# HW1_13.net
KiCad netlist of a schematic drawn in EasyEDA
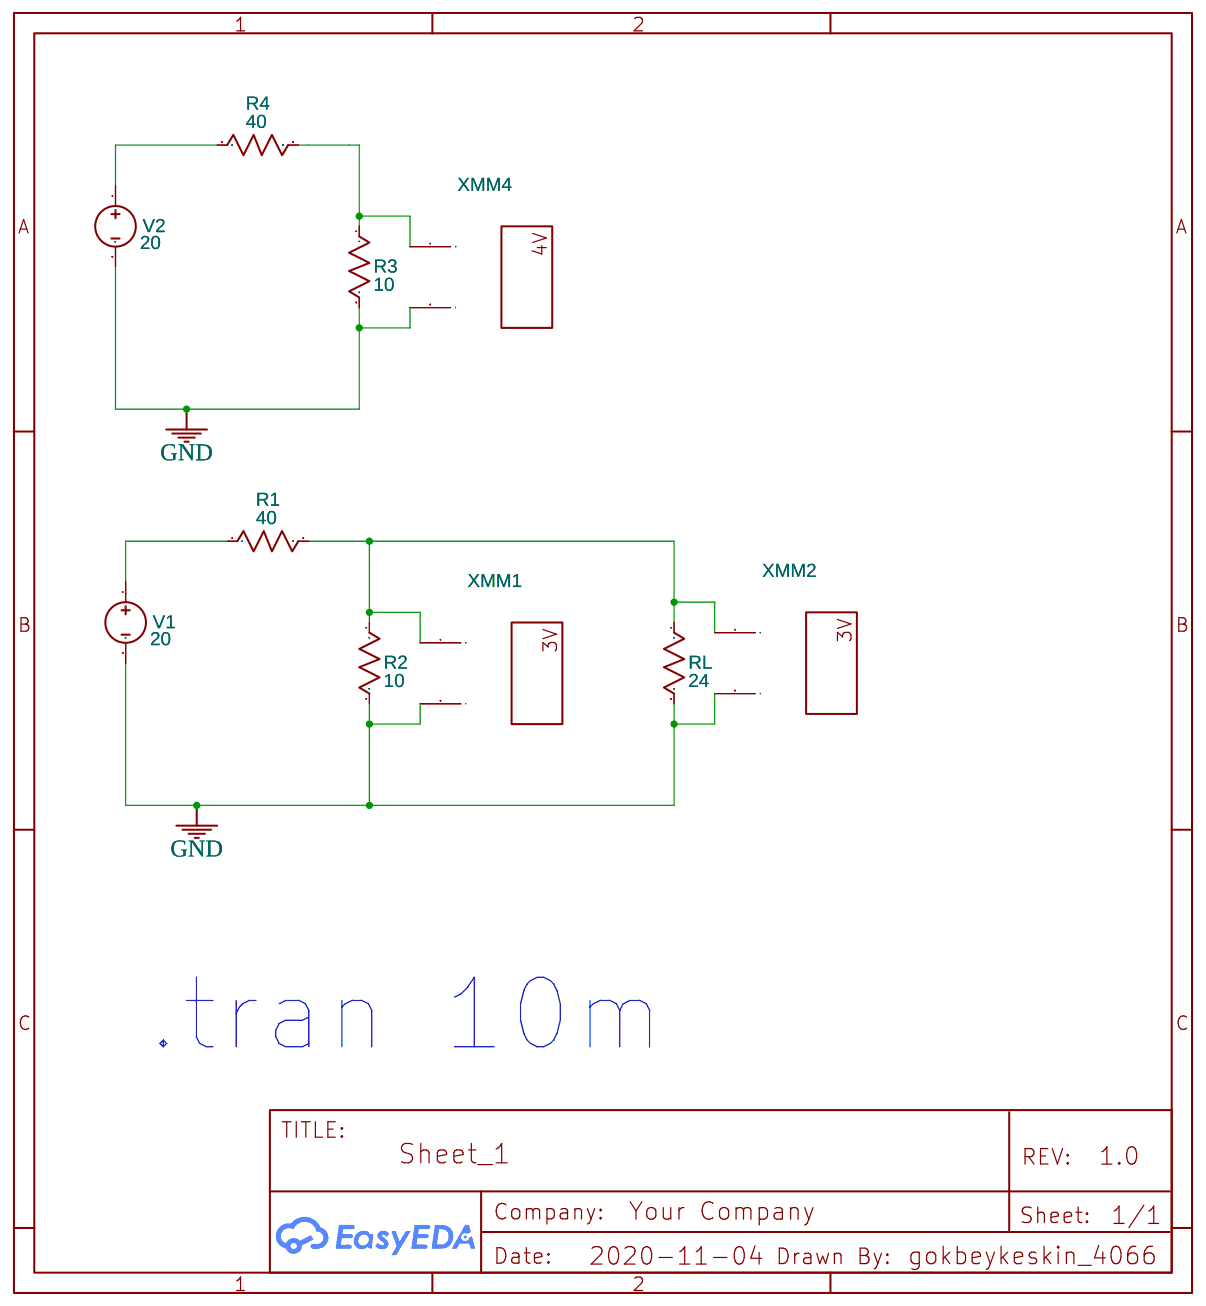
[diagram p0: schematic sheet]

(export (version "E")
  (design (tool "Eeschema 10.0.6"))
  (components
    (comp (ref "R1") (value "40") (libsource (lib "") (part "Resistor_US_2")))
    (comp (ref "R2") (value "10") (libsource (lib "") (part "Resistor_US")))
    (comp (ref "R3") (value "10") (libsource (lib "") (part "Resistor_US")))
    (comp (ref "R4") (value "40") (libsource (lib "") (part "Resistor_US_2")))
    (comp (ref "RL") (value "24") (libsource (lib "") (part "Resistor_US_1")))
    (comp (ref "V1") (value "20") (libsource (lib "") (part "VDC")))
    (comp (ref "V2") (value "20") (libsource (lib "") (part "VDC")))
    (comp (ref "XMM1") (value "Multimeter") (libsource (lib "") (part "MULTIMETER_1")))
    (comp (ref "XMM2") (value "Multimeter") (libsource (lib "") (part "MULTIMETER_1")))
    (comp (ref "XMM4") (value "Multimeter") (libsource (lib "") (part "MULTIMETER")))
  )
  (nets
    (net (code "1") (name "GND") (class "Default")
      (node (ref "R2") (pin "2") (pinfunction "2_2") (pintype "unspecified"))
      (node (ref "R3") (pin "2") (pinfunction "2_2") (pintype "unspecified"))
      (node (ref "RL") (pin "2") (pinfunction "2_2") (pintype "unspecified"))
      (node (ref "V1") (pin "2") (pinfunction "2_2") (pintype "unspecified"))
      (node (ref "V2") (pin "2") (pinfunction "2_2") (pintype "unspecified"))
      (node (ref "XMM1") (pin "2") (pinfunction "I_2") (pintype "unspecified"))
      (node (ref "XMM2") (pin "2") (pinfunction "I_2") (pintype "unspecified"))
      (node (ref "XMM4") (pin "2") (pinfunction "I_2") (pintype "unspecified"))
    )
    (net (code "2") (name "Net-(R1-Pad1)") (class "Default")
      (node (ref "R1") (pin "1") (pinfunction "1_1") (pintype "unspecified"))
      (node (ref "V1") (pin "1") (pinfunction "1_1") (pintype "unspecified"))
    )
    (net (code "3") (name "Net-(R4-Pad1)") (class "Default")
      (node (ref "R4") (pin "1") (pinfunction "1_1") (pintype "unspecified"))
      (node (ref "V2") (pin "1") (pinfunction "1_1") (pintype "unspecified"))
    )
    (net (code "4") (name "Net-(XMM1-+)") (class "Default")
      (node (ref "R1") (pin "2") (pinfunction "2_2") (pintype "unspecified"))
      (node (ref "R2") (pin "1") (pinfunction "1_1") (pintype "unspecified"))
      (node (ref "RL") (pin "1") (pinfunction "1_1") (pintype "unspecified"))
      (node (ref "XMM1") (pin "1") (pinfunction "+_1") (pintype "unspecified"))
      (node (ref "XMM2") (pin "1") (pinfunction "+_1") (pintype "unspecified"))
    )
    (net (code "5") (name "Net-(XMM4-+)") (class "Default")
      (node (ref "R3") (pin "1") (pinfunction "1_1") (pintype "unspecified"))
      (node (ref "R4") (pin "2") (pinfunction "2_2") (pintype "unspecified"))
      (node (ref "XMM4") (pin "1") (pinfunction "+_1") (pintype "unspecified"))
    )
  )
)
